# Transistor_Block.net
KiCad netlist of a schematic drawn in Altium Designer
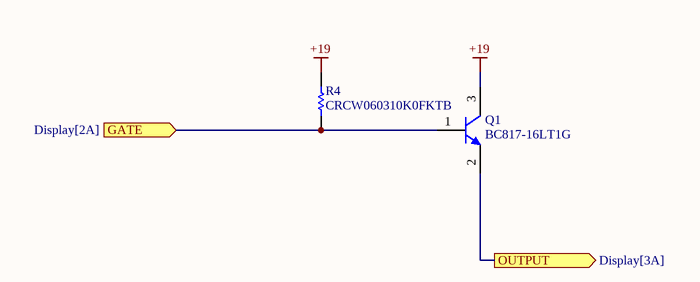
[diagram p0: Transistor_Block.SchDoc]

(export (version "E")
  (design (tool "Eeschema 10.0.6"))
  (components
    (comp (ref "Q1")
      (value "BC817-16LT1G")
      (footprint "ONSC-SOT-23-3-318-08_V")
      (description "General Purpose Transistor, NPN Silicon, 3-Pin SOT-23, Pb-Free, Tape and Reel")
      (fields (field (name "MANUFACTURER") "On Semiconductor"))
      (libsource (lib "Altium Content Vault") (part "ONSC-NPN-B1E2C3-3"))
    )
    (comp (ref "R4")
      (value "CRCW060310K0FKTB")
      (footprint "RESC1609X50X30ML10T20")
      (fields (field (name "MANUFACTURER") "Vishay Dale"))
      (libsource (lib "Altium Content Vault") (part "RES"))
    )
  )
  (nets
    (net (code "1") (name "+19") (class "Default")
      (node (ref "Q1") (pin "3") (pinfunction "C_3") (pintype "passive"))
      (node (ref "R4") (pin "2") (pinfunction "2_2") (pintype "passive"))
    )
    (net (code "2") (name "/GATE") (class "Default")
      (node (ref "Q1") (pin "1") (pinfunction "B_1") (pintype "passive"))
      (node (ref "R4") (pin "1") (pinfunction "1_1") (pintype "passive"))
    )
    (net (code "3") (name "/OUTPUT") (class "Default")
      (node (ref "Q1") (pin "2") (pinfunction "E_2") (pintype "passive"))
    )
  )
)
